# ArduHoop.net
KiCad netlist of a schematic drawn in Altium Designer
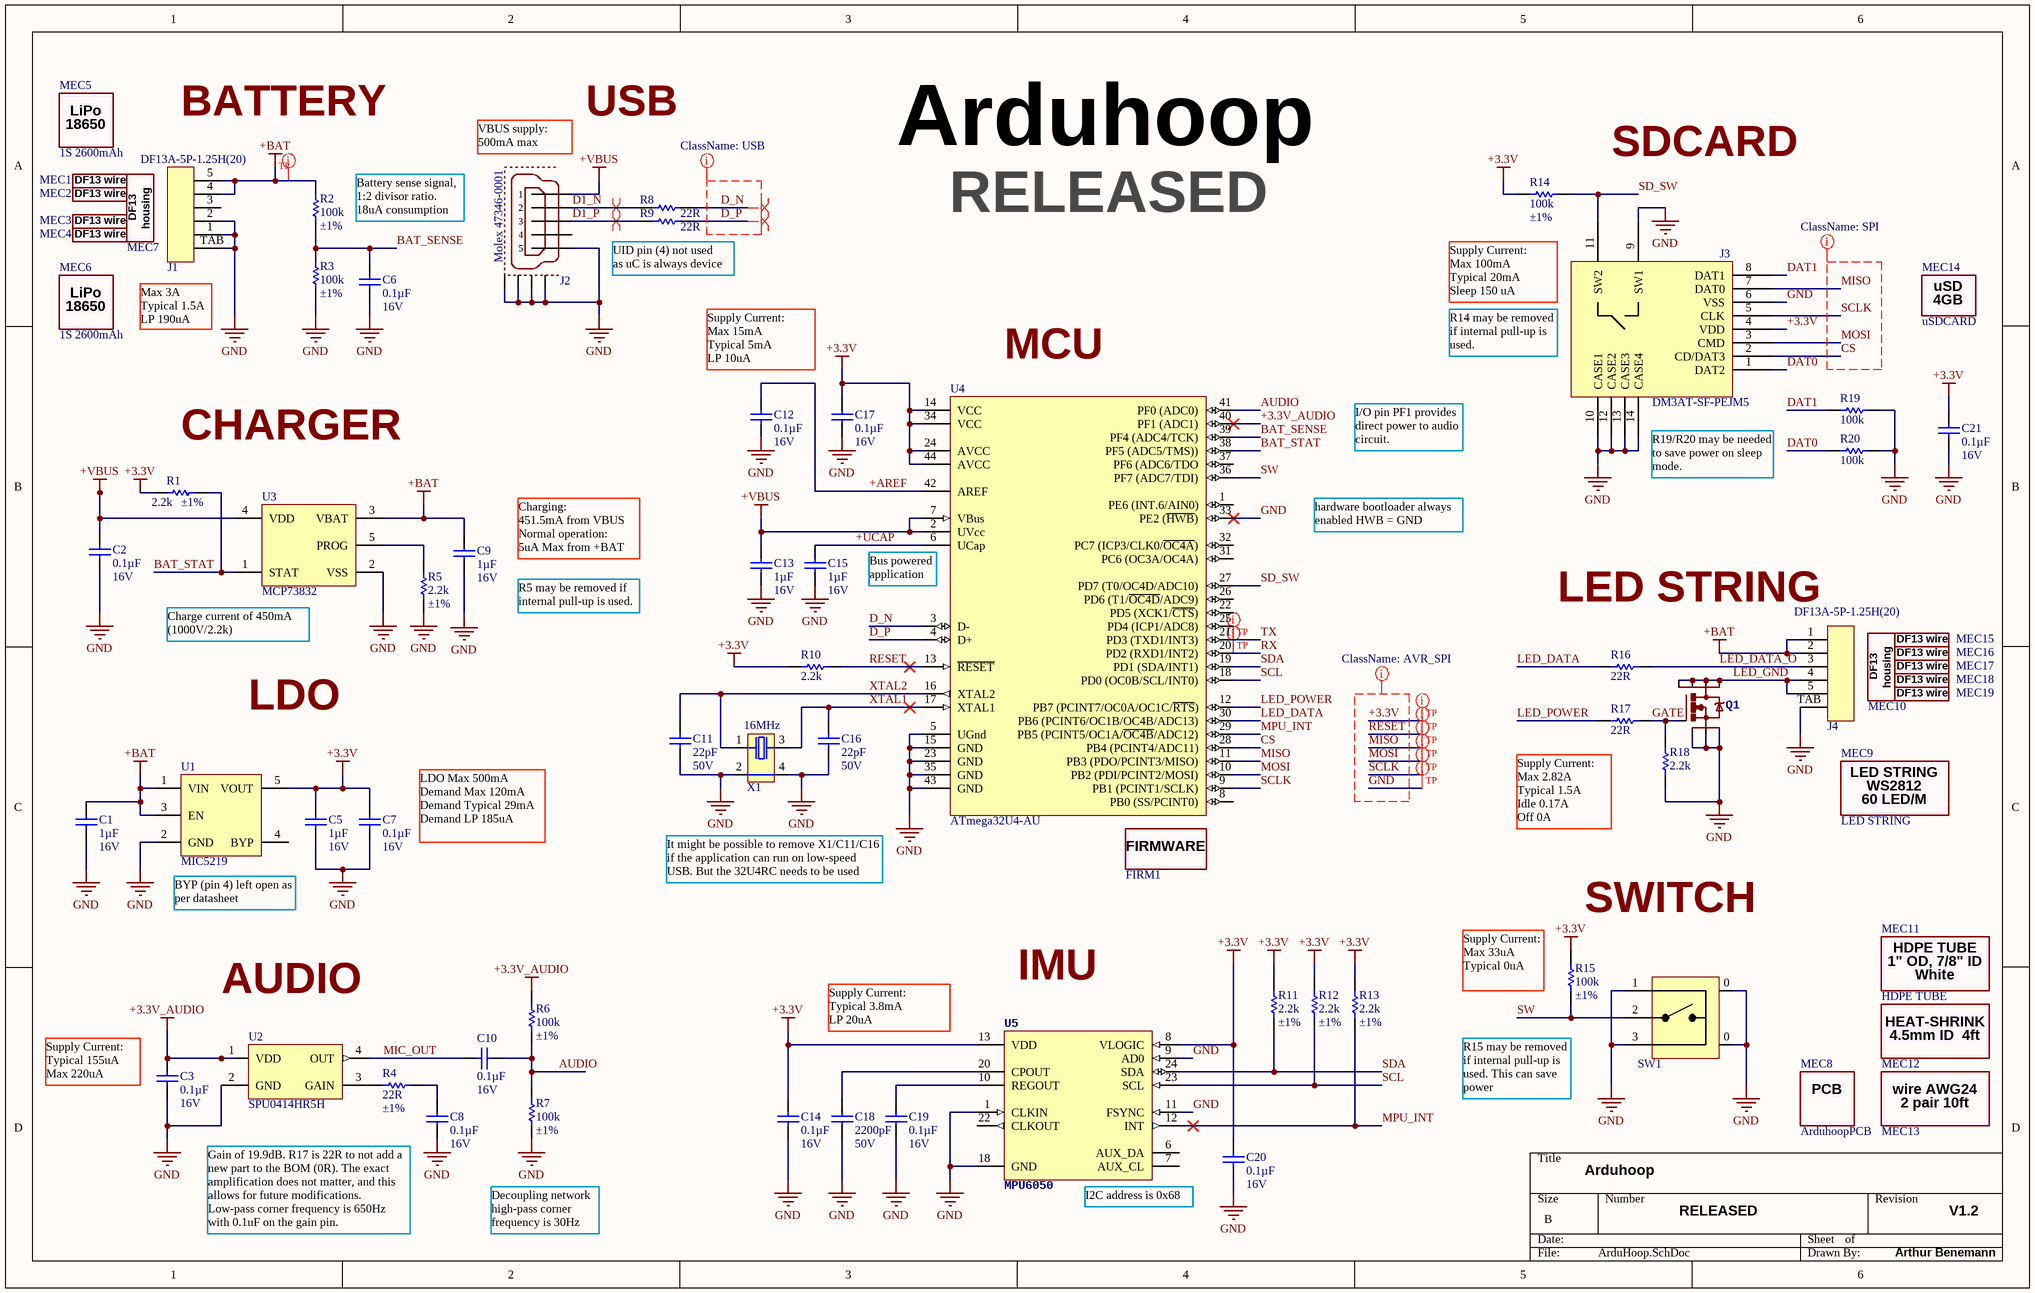
[diagram p0: ArduHoop.SchDoc]

(export (version "E")
  (design (tool "Eeschema 10.0.6"))
  (components
    (comp (ref "C1")
      (value "1µF")
      (footprint "C0603")
      (description "CAP CER 1UF 16V X7R 0603")
      (fields
        (field (name "VOLTAGE") "16V")
        (field (name "PART NUMBER") "C01293")
        (field (name "MANUFACTURER") "Murata Electronics North America")
      )
      (libsource (lib "open-components") (part "CAP"))
    )
    (comp (ref "C2")
      (value "0.1µF")
      (footprint "C0603")
      (description "CAP CER 0.1UF 16V X7R 0603")
      (fields
        (field (name "VOLTAGE") "16V")
        (field (name "PART NUMBER") "C01052")
        (field (name "MANUFACTURER") "Murata Electronics North America")
      )
      (libsource (lib "open-components") (part "CAP"))
    )
    (comp (ref "C3")
      (value "0.1µF")
      (footprint "C0603")
      (description "CAP CER 0.1UF 16V X7R 0603")
      (fields
        (field (name "VOLTAGE") "16V")
        (field (name "PART NUMBER") "C01052")
        (field (name "MANUFACTURER") "Murata Electronics North America")
      )
      (libsource (lib "open-components") (part "CAP"))
    )
    (comp (ref "C5")
      (value "1µF")
      (footprint "C0603")
      (description "CAP CER 1UF 16V X7R 0603")
      (fields
        (field (name "VOLTAGE") "16V")
        (field (name "PART NUMBER") "C01293")
        (field (name "MANUFACTURER") "Murata Electronics North America")
      )
      (libsource (lib "open-components") (part "CAP"))
    )
    (comp (ref "C6")
      (value "0.1µF")
      (footprint "C0603")
      (description "CAP CER 0.1UF 16V X7R 0603")
      (fields
        (field (name "VOLTAGE") "16V")
        (field (name "PART NUMBER") "C01052")
        (field (name "MANUFACTURER") "Murata Electronics North America")
      )
      (libsource (lib "open-components") (part "CAP"))
    )
    (comp (ref "C7")
      (value "0.1µF")
      (footprint "C0603")
      (description "CAP CER 0.1UF 16V X7R 0603")
      (fields
        (field (name "VOLTAGE") "16V")
        (field (name "PART NUMBER") "C01052")
        (field (name "MANUFACTURER") "Murata Electronics North America")
      )
      (libsource (lib "open-components") (part "CAP"))
    )
    (comp (ref "C8")
      (value "0.1µF")
      (footprint "C0603")
      (description "CAP CER 0.1UF 16V X7R 0603")
      (fields
        (field (name "VOLTAGE") "16V")
        (field (name "PART NUMBER") "C01052")
        (field (name "MANUFACTURER") "Murata Electronics North America")
      )
      (libsource (lib "open-components") (part "CAP"))
    )
    (comp (ref "C9")
      (value "1µF")
      (footprint "C0603")
      (description "CAP CER 1UF 16V X7R 0603")
      (fields
        (field (name "VOLTAGE") "16V")
        (field (name "PART NUMBER") "C01293")
        (field (name "MANUFACTURER") "Murata Electronics North America")
      )
      (libsource (lib "open-components") (part "CAP"))
    )
    (comp (ref "C10")
      (value "0.1µF")
      (footprint "C0603")
      (description "CAP CER 0.1UF 16V X7R 0603")
      (fields
        (field (name "VOLTAGE") "16V")
        (field (name "PART NUMBER") "C01052")
        (field (name "MANUFACTURER") "Murata Electronics North America")
      )
      (libsource (lib "open-components") (part "CAP"))
    )
    (comp (ref "C11")
      (value "22pF")
      (footprint "C0603")
      (description "CAP CER 22PF 50V NP0 0603")
      (fields
        (field (name "VOLTAGE") "50V")
        (field (name "PART NUMBER") "C00144")
        (field (name "MANUFACTURER") "Murata Electronics North America")
      )
      (libsource (lib "open-components") (part "CAP"))
    )
    (comp (ref "C12")
      (value "0.1µF")
      (footprint "C0603")
      (description "CAP CER 0.1UF 16V X7R 0603")
      (fields
        (field (name "VOLTAGE") "16V")
        (field (name "PART NUMBER") "C01052")
        (field (name "MANUFACTURER") "Murata Electronics North America")
      )
      (libsource (lib "open-components") (part "CAP"))
    )
    (comp (ref "C13")
      (value "1µF")
      (footprint "C0603")
      (description "CAP CER 1UF 16V X7R 0603")
      (fields
        (field (name "VOLTAGE") "16V")
        (field (name "PART NUMBER") "C01293")
        (field (name "MANUFACTURER") "Murata Electronics North America")
      )
      (libsource (lib "open-components") (part "CAP"))
    )
    (comp (ref "C14")
      (value "0.1µF")
      (footprint "C0603")
      (description "CAP CER 0.1UF 16V X7R 0603")
      (fields
        (field (name "VOLTAGE") "16V")
        (field (name "PART NUMBER") "C01052")
        (field (name "MANUFACTURER") "Murata Electronics North America")
      )
      (libsource (lib "open-components") (part "CAP"))
    )
    (comp (ref "C15")
      (value "1µF")
      (footprint "C0603")
      (description "CAP CER 1UF 16V X7R 0603")
      (fields
        (field (name "VOLTAGE") "16V")
        (field (name "PART NUMBER") "C01293")
        (field (name "MANUFACTURER") "Murata Electronics North America")
      )
      (libsource (lib "open-components") (part "CAP"))
    )
    (comp (ref "C16")
      (value "22pF")
      (footprint "C0603")
      (description "CAP CER 22PF 50V NP0 0603")
      (fields
        (field (name "VOLTAGE") "50V")
        (field (name "PART NUMBER") "C00144")
        (field (name "MANUFACTURER") "Murata Electronics North America")
      )
      (libsource (lib "open-components") (part "CAP"))
    )
    (comp (ref "C17")
      (value "0.1µF")
      (footprint "C0603")
      (description "CAP CER 0.1UF 16V X7R 0603")
      (fields
        (field (name "VOLTAGE") "16V")
        (field (name "PART NUMBER") "C01052")
        (field (name "MANUFACTURER") "Murata Electronics North America")
      )
      (libsource (lib "open-components") (part "CAP"))
    )
    (comp (ref "C18")
      (value "2200pF")
      (footprint "C0603")
      (description "CAP CER 2200PF 50V X7R 0603")
      (fields
        (field (name "VOLTAGE") "50V")
        (field (name "PART NUMBER") "C00648")
        (field (name "MANUFACTURER") "Murata Electronics North America")
      )
      (libsource (lib "open-components") (part "CAP"))
    )
    (comp (ref "C19")
      (value "0.1µF")
      (footprint "C0603")
      (description "CAP CER 0.1UF 16V X7R 0603")
      (fields
        (field (name "VOLTAGE") "16V")
        (field (name "PART NUMBER") "C01052")
        (field (name "MANUFACTURER") "Murata Electronics North America")
      )
      (libsource (lib "open-components") (part "CAP"))
    )
    (comp (ref "C20")
      (value "0.1µF")
      (footprint "C0603")
      (description "CAP CER 0.1UF 16V X7R 0603")
      (fields
        (field (name "VOLTAGE") "16V")
        (field (name "PART NUMBER") "C01052")
        (field (name "MANUFACTURER") "Murata Electronics North America")
      )
      (libsource (lib "open-components") (part "CAP"))
    )
    (comp (ref "C21")
      (value "0.1µF")
      (footprint "C0603")
      (description "CAP CER 0.1UF 16V X7R 0603")
      (fields
        (field (name "VOLTAGE") "16V")
        (field (name "PART NUMBER") "C01052")
        (field (name "MANUFACTURER") "Murata Electronics North America")
      )
      (libsource (lib "open-components") (part "CAP"))
    )
    (comp (ref "FIRM1") (value "FIRMWARE") (libsource (lib "extraComponents") (part "FIRMWARE")))
    (comp (ref "J1")
      (value "HDR_TAB_1x5")
      (footprint "DF13A-5P-1.25H")
      (description "CONN HEADER 5POS 1.25MM R/A TIN")
      (fields
        (field (name "PART NUMBER") "J00022")
        (field (name "MANUFACTURER") "Hirose Electric Co Ltd")
        (field (name "MANUFACTURER PART NUMBER") "DF13A-5P-1.25H(20)")
      )
      (libsource (lib "") (part "HDR_TAB_1x5_1"))
    )
    (comp (ref "J2") (value "~") (footprint "Molex 47346-0001") (libsource (lib "3DR") (part "USB")))
    (comp (ref "J3")
      (value "DM3AT-SF-PEJM5")
      (footprint "USD_DM3AT")
      (description "CONN MICRO SD CARD PUSH-PUSH R/A")
      (fields (field (name "PART NUMBER") "J00167") (field (name "MANUFACTURER") "Hirose Electric Co Ltd"))
      (libsource (lib "open-components") (part "uSD_DM3AT-SF-PEJM5"))
    )
    (comp (ref "J4")
      (value "HDR_TAB_1x5")
      (footprint "DF13A-5P-1.25H")
      (description "CONN HEADER 5POS 1.25MM R/A TIN")
      (fields
        (field (name "PART NUMBER") "J00022")
        (field (name "MANUFACTURER") "Hirose Electric Co Ltd")
        (field (name "MANUFACTURER PART NUMBER") "DF13A-5P-1.25H(20)")
      )
      (libsource (lib "open-components") (part "HDR_TAB_1x5"))
    )
    (comp (ref "MEC1")
      (value "wire5inch-df13")
      (description "DF13 pre-crimped 5\" wire")
      (fields
        (field (name "MANUFACTURER") "Hirose Electric Co Ltd")
        (field (name "MANUFACTURER PART NUMBER") "H4BXG-10105-W6")
      )
      (libsource (lib "extraComponents") (part "wire5inch-df13"))
    )
    (comp (ref "MEC2")
      (value "wire5inch-df13")
      (description "DF13 pre-crimped 5\" wire")
      (fields
        (field (name "MANUFACTURER") "Hirose Electric Co Ltd")
        (field (name "MANUFACTURER PART NUMBER") "H4BXG-10105-W6")
      )
      (libsource (lib "extraComponents") (part "wire5inch-df13"))
    )
    (comp (ref "MEC3")
      (value "wire5inch-df13")
      (description "DF13 pre-crimped 5\" wire")
      (fields
        (field (name "MANUFACTURER") "Hirose Electric Co Ltd")
        (field (name "MANUFACTURER PART NUMBER") "H4BXG-10105-W6")
      )
      (libsource (lib "extraComponents") (part "wire5inch-df13"))
    )
    (comp (ref "MEC4")
      (value "wire5inch-df13")
      (description "DF13 pre-crimped 5\" wire")
      (fields
        (field (name "MANUFACTURER") "Hirose Electric Co Ltd")
        (field (name "MANUFACTURER PART NUMBER") "H4BXG-10105-W6")
      )
      (libsource (lib "extraComponents") (part "wire5inch-df13"))
    )
    (comp (ref "MEC5")
      (value "1S 2600mAh")
      (description "Tenergy Li-Ion 18650 3.7V 2600mAh")
      (fields (field (name "MANUFACTURER PART NUMBER") "30011") (field (name "MANUFACTURER") "Tenergy"))
      (libsource (lib "extraComponents") (part "LiPo_18650_2600mAh"))
    )
    (comp (ref "MEC6")
      (value "1S 2600mAh")
      (description "Tenergy Li-Ion 18650 3.7V 2600mAh")
      (fields (field (name "MANUFACTURER PART NUMBER") "30011") (field (name "MANUFACTURER") "Tenergy"))
      (libsource (lib "extraComponents") (part "LiPo_18650_2600mAh"))
    )
    (comp (ref "MEC7")
      (value "df13housing")
      (description "DF13 housing 5pos")
      (fields
        (field (name "MANUFACTURER") "Hirose Electric Co Ltd")
        (field (name "MANUFACTURER PART NUMBER") "H4BXG-10105-W6")
      )
      (libsource (lib "extraComponents") (part "df13housing"))
    )
    (comp (ref "MEC8")
      (value "ArduhoopPCB")
      (description "PCB")
      (libsource (lib "extraComponents") (part "PCB"))
    )
    (comp (ref "MEC9")
      (value "LED STRING")
      (description "LED Strip WS2812B 60 LEDs/meter")
      (libsource (lib "") (part "LED_STRING1_1"))
    )
    (comp (ref "MEC10")
      (value "df13housing")
      (description "DF13 housing 5pos")
      (fields
        (field (name "MANUFACTURER") "Hirose Electric Co Ltd")
        (field (name "MANUFACTURER PART NUMBER") "H4BXG-10105-W6")
      )
      (libsource (lib "extraComponents") (part "df13housing"))
    )
    (comp (ref "MEC11")
      (value "HDPE TUBE")
      (description "HDPE TUBE 1\" OD, 7/8\" ID White 10 ft")
      (libsource (lib "extraComponents") (part "TUBE_HDPE"))
    )
    (comp (ref "MEC12")
      (value "heatshrink")
      (description "HEAT-SHRINK 3/16\" ID Before, 3/32\" ID After, 4' Length")
      (libsource (lib "extraComponents") (part "heatshrink"))
    )
    (comp (ref "MEC13")
      (value "WIRE AWG24")
      (description "WIRE AWG24 2 conductors")
      (libsource (lib "extraComponents") (part "WIRE_AWG24"))
    )
    (comp (ref "MEC14")
      (value "uSDCARD")
      (description "Sandisk 4GB microSDHC Card Class 2")
      (libsource (lib "extraComponents") (part "LED_STRING1"))
    )
    (comp (ref "MEC15")
      (value "wire5inch-df13")
      (description "DF13 pre-crimped 5\" wire")
      (fields
        (field (name "MANUFACTURER") "Hirose Electric Co Ltd")
        (field (name "MANUFACTURER PART NUMBER") "H4BXG-10105-W6")
      )
      (libsource (lib "extraComponents") (part "wire5inch-df13"))
    )
    (comp (ref "MEC16")
      (value "wire5inch-df13")
      (description "DF13 pre-crimped 5\" wire")
      (fields
        (field (name "MANUFACTURER") "Hirose Electric Co Ltd")
        (field (name "MANUFACTURER PART NUMBER") "H4BXG-10105-W6")
      )
      (libsource (lib "extraComponents") (part "wire5inch-df13"))
    )
    (comp (ref "MEC17")
      (value "wire5inch-df13")
      (description "DF13 pre-crimped 5\" wire")
      (fields
        (field (name "MANUFACTURER") "Hirose Electric Co Ltd")
        (field (name "MANUFACTURER PART NUMBER") "H4BXG-10105-W6")
      )
      (libsource (lib "extraComponents") (part "wire5inch-df13"))
    )
    (comp (ref "MEC18")
      (value "wire5inch-df13")
      (description "DF13 pre-crimped 5\" wire")
      (fields
        (field (name "MANUFACTURER") "Hirose Electric Co Ltd")
        (field (name "MANUFACTURER PART NUMBER") "H4BXG-10105-W6")
      )
      (libsource (lib "extraComponents") (part "wire5inch-df13"))
    )
    (comp (ref "MEC19")
      (value "wire5inch-df13")
      (description "DF13 pre-crimped 5\" wire")
      (fields
        (field (name "MANUFACTURER") "Hirose Electric Co Ltd")
        (field (name "MANUFACTURER PART NUMBER") "H4BXG-10105-W6")
      )
      (libsource (lib "extraComponents") (part "wire5inch-df13"))
    )
    (comp (ref "Q1")
      (value "MOSFET_N")
      (footprint "SO-8")
      (description "MOSFET P-CH 30V 5.8A 8-SOIC")
      (fields (field (name "PART NUMBER") "Q000008") (field (name "MANUFACTURER PART NUMBER") "IRF7406TRPBF"))
      (libsource (lib "open-components") (part "MOSFET_N"))
    )
    (comp (ref "R1")
      (value "2.2k")
      (footprint "R0603")
      (description "RES SMD 2.2K OHM 1% 1/10W 0603")
      (fields
        (field (name "TOLERANCE") "±1%")
        (field (name "PART NUMBER") "R00109")
        (field (name "MANUFACTURER") "Yageo")
      )
      (libsource (lib "open-components") (part "RES"))
    )
    (comp (ref "R2")
      (value "100k")
      (footprint "R0603")
      (description "RES SMD 100K OHM 1% 1/10W 0603")
      (fields
        (field (name "TOLERANCE") "±1%")
        (field (name "PART NUMBER") "R00189")
        (field (name "MANUFACTURER") "Yageo")
      )
      (libsource (lib "open-components") (part "RES"))
    )
    (comp (ref "R3")
      (value "100k")
      (footprint "R0603")
      (description "RES SMD 100K OHM 1% 1/10W 0603")
      (fields
        (field (name "TOLERANCE") "±1%")
        (field (name "PART NUMBER") "R00189")
        (field (name "MANUFACTURER") "Yageo")
      )
      (libsource (lib "open-components") (part "RES"))
    )
    (comp (ref "R4")
      (value "22R")
      (footprint "R0603")
      (description "RES SMD 22 OHM 1% 1/10W 0603")
      (fields
        (field (name "TOLERANCE") "±1%")
        (field (name "PART NUMBER") "R00015")
        (field (name "MANUFACTURER") "Yageo")
      )
      (libsource (lib "open-components") (part "RES"))
    )
    (comp (ref "R5")
      (value "2.2k")
      (footprint "R0603")
      (description "RES SMD 2.2K OHM 1% 1/10W 0603")
      (fields
        (field (name "TOLERANCE") "±1%")
        (field (name "PART NUMBER") "R00109")
        (field (name "MANUFACTURER") "Yageo")
      )
      (libsource (lib "open-components") (part "RES"))
    )
    (comp (ref "R6")
      (value "100k")
      (footprint "R0603")
      (description "RES SMD 100K OHM 1% 1/10W 0603")
      (fields
        (field (name "TOLERANCE") "±1%")
        (field (name "PART NUMBER") "R00189")
        (field (name "MANUFACTURER") "Yageo")
      )
      (libsource (lib "open-components") (part "RES"))
    )
    (comp (ref "R7")
      (value "100k")
      (footprint "R0603")
      (description "RES SMD 100K OHM 1% 1/10W 0603")
      (fields
        (field (name "TOLERANCE") "±1%")
        (field (name "PART NUMBER") "R00189")
        (field (name "MANUFACTURER") "Yageo")
      )
      (libsource (lib "open-components") (part "RES"))
    )
    (comp (ref "R8")
      (value "22R")
      (footprint "R0603")
      (description "RES SMD 22 OHM 1% 1/10W 0603")
      (fields (field (name "TOLERANCE") "±1%") (field (name "PART NUMBER") "R00015"))
      (libsource (lib "open-components") (part "RES"))
    )
    (comp (ref "R9")
      (value "22R")
      (footprint "R0603")
      (description "RES SMD 22 OHM 1% 1/10W 0603")
      (fields (field (name "TOLERANCE") "±1%") (field (name "PART NUMBER") "R00015"))
      (libsource (lib "open-components") (part "RES"))
    )
    (comp (ref "R10")
      (value "2.2k")
      (footprint "R0603")
      (description "RES SMD 2.2K OHM 1% 1/10W 0603")
      (fields (field (name "PART NUMBER") "R00109") (field (name "MANUFACTURER") "Yageo"))
      (libsource (lib "open-components") (part "RES"))
    )
    (comp (ref "R11")
      (value "2.2k")
      (footprint "R0603")
      (description "RES SMD 2.2K OHM 1% 1/10W 0603")
      (fields
        (field (name "TOLERANCE") "±1%")
        (field (name "PART NUMBER") "R00109")
        (field (name "MANUFACTURER") "Yageo")
      )
      (libsource (lib "open-components") (part "RES"))
    )
    (comp (ref "R12")
      (value "2.2k")
      (footprint "R0603")
      (description "RES SMD 2.2K OHM 1% 1/10W 0603")
      (fields
        (field (name "TOLERANCE") "±1%")
        (field (name "PART NUMBER") "R00109")
        (field (name "MANUFACTURER") "Yageo")
      )
      (libsource (lib "open-components") (part "RES"))
    )
    (comp (ref "R13")
      (value "2.2k")
      (footprint "R0603")
      (description "RES SMD 2.2K OHM 1% 1/10W 0603")
      (fields
        (field (name "TOLERANCE") "±1%")
        (field (name "PART NUMBER") "R00109")
        (field (name "MANUFACTURER") "Yageo")
      )
      (libsource (lib "open-components") (part "RES"))
    )
    (comp (ref "R14")
      (value "100k")
      (footprint "R0603")
      (description "RES SMD 100K OHM 1% 1/10W 0603")
      (fields
        (field (name "TOLERANCE") "±1%")
        (field (name "PART NUMBER") "R00189")
        (field (name "MANUFACTURER") "Yageo")
      )
      (libsource (lib "open-components") (part "RES"))
    )
    (comp (ref "R15")
      (value "100k")
      (footprint "R0603")
      (description "RES SMD 100K OHM 1% 1/10W 0603")
      (fields
        (field (name "TOLERANCE") "±1%")
        (field (name "PART NUMBER") "R00189")
        (field (name "MANUFACTURER") "Yageo")
      )
      (libsource (lib "open-components") (part "RES"))
    )
    (comp (ref "R16")
      (value "22R")
      (footprint "R0603")
      (description "RES SMD 22 OHM 1% 1/10W 0603")
      (fields (field (name "PART NUMBER") "R00015") (field (name "MANUFACTURER") "Yageo"))
      (libsource (lib "open-components") (part "RES"))
    )
    (comp (ref "R17")
      (value "22R")
      (footprint "R0603")
      (description "RES SMD 22 OHM 1% 1/10W 0603")
      (fields (field (name "PART NUMBER") "R00015") (field (name "MANUFACTURER") "Yageo"))
      (libsource (lib "open-components") (part "RES"))
    )
    (comp (ref "R18")
      (value "2.2k")
      (footprint "R0603")
      (description "RES SMD 2.2K OHM 1% 1/10W 0603")
      (fields (field (name "PART NUMBER") "R00109") (field (name "MANUFACTURER") "Yageo"))
      (libsource (lib "open-components") (part "RES"))
    )
    (comp (ref "R19")
      (value "100k")
      (footprint "R0603")
      (description "RES SMD 100K OHM 1% 1/10W 0603")
      (fields (field (name "PART NUMBER") "R00189") (field (name "MANUFACTURER") "Yageo"))
      (libsource (lib "open-components") (part "RES"))
    )
    (comp (ref "R20")
      (value "100k")
      (footprint "R0603")
      (description "RES SMD 100K OHM 1% 1/10W 0603")
      (fields (field (name "PART NUMBER") "R00189") (field (name "MANUFACTURER") "Yageo"))
      (libsource (lib "open-components") (part "RES"))
    )
    (comp (ref "SW1")
      (value "EVPAE")
      (footprint "EVPAEJB2A")
      (description "SWITCH TACTILE SPST-NO 0.02A 15V")
      (fields
        (field (name "PART NUMBER") "SW000001")
        (field (name "MANUFACTURER") "Panasonic Electronic Components")
      )
      (libsource (lib "open-components") (part "EVPAE"))
    )
    (comp (ref "U1")
      (value "MIC5219")
      (footprint "SOT-23-5")
      (description "IC REG LDO 3.3V 0.5A SOT23-5")
      (fields
        (field (name "PART NUMBER") "PMIC000001")
        (field (name "MANUFACTURER PART NUMBER") "MIC5219-3.3YM5-TR")
      )
      (libsource (lib "open-components") (part "MIC5219"))
    )
    (comp (ref "U2")
      (value "SPU0414HR5H")
      (footprint "SPU0414HR5H")
      (description "MIC MEMS ANALOG OMNI -22DB")
      (fields
        (field (name "PART NUMBER") "P000005")
        (field (name "MANUFACTURER PART NUMBER") "SPU0414HR5H-SB-7")
      )
      (libsource (lib "open-components") (part "SPU0414HR5H"))
    )
    (comp (ref "U3")
      (value "MCP73832")
      (footprint "SOT-23-5")
      (description "IC LI-ION/LI-POLY CTRLR SOT23-5")
      (fields
        (field (name "PART NUMBER") "P000002")
        (field (name "MANUFACTURER PART NUMBER") "MCP73832T-2ATI/OT")
      )
      (libsource (lib "open-components") (part "MCP7383x"))
    )
    (comp (ref "U4")
      (value "ATmega32U4-AU")
      (footprint "ATMEL-TQFP44_ml")
      (description "IC MCU 8BIT 32KB FLASH 44TQFP")
      (fields
        (field (name "PART NUMBER") "MCU00751")
        (field (name "MANUFACTURER PART NUMBER") "ATMEGA32U4-AUR")
      )
      (libsource (lib "open-components") (part "ATmega32U4-AU"))
    )
    (comp (ref "U5")
      (value "MPU6050")
      (footprint "QFN24_4X4X0.9mm")
      (description "GYRO/ACCELEROMETER 6AXIS 24QFN")
      (fields (field (name "PART NUMBER") "P000004") (field (name "MANUFACTURER PART NUMBER") "MPU-6050"))
      (libsource (lib "open-components") (part "MPU6050"))
    )
    (comp (ref "X1")
      (value "Crystal_4pin")
      (footprint "SMD4_3.2x2.50mm_ABM8")
      (description "CRYSTAL 16.0000MHZ 18PF SMD")
      (fields
        (field (name "PART NUMBER") "Q00342")
        (field (name "MANUFACTURER PART NUMBER") "ABM8-16.000MHZ-B2-T")
        (field (name "FREQUENCY") "16MHz")
      )
      (libsource (lib "open-components") (part "Crystal_4pin"))
    )
  )
  (nets
    (net (code "1") (name "+3.3V") (class "Default")
      (node (ref "C14") (pin "1") (pinfunction "1_1") (pintype "passive"))
      (node (ref "C17") (pin "1") (pinfunction "1_1") (pintype "passive"))
      (node (ref "C20") (pin "1") (pinfunction "1_1") (pintype "passive"))
      (node (ref "C21") (pin "1") (pinfunction "1_1") (pintype "passive"))
      (node (ref "C5") (pin "1") (pinfunction "1_1") (pintype "passive"))
      (node (ref "C7") (pin "1") (pinfunction "1_1") (pintype "passive"))
      (node (ref "J3") (pin "4") (pinfunction "VDD_4") (pintype "passive"))
      (node (ref "R1") (pin "1") (pinfunction "1_1") (pintype "passive"))
      (node (ref "R10") (pin "1") (pinfunction "1_1") (pintype "passive"))
      (node (ref "R11") (pin "1") (pinfunction "1_1") (pintype "passive"))
      (node (ref "R12") (pin "1") (pinfunction "1_1") (pintype "passive"))
      (node (ref "R13") (pin "1") (pinfunction "1_1") (pintype "passive"))
      (node (ref "R14") (pin "2") (pinfunction "2_2") (pintype "passive"))
      (node (ref "R15") (pin "2") (pinfunction "2_2") (pintype "passive"))
      (node (ref "U1") (pin "5") (pinfunction "VOUT_5") (pintype "power_in"))
      (node (ref "U4") (pin "14") (pinfunction "VCC_14") (pintype "power_in"))
      (node (ref "U4") (pin "24") (pinfunction "AVCC_24") (pintype "power_in"))
      (node (ref "U4") (pin "34") (pinfunction "VCC_34") (pintype "power_in"))
      (node (ref "U4") (pin "44") (pinfunction "AVCC_44") (pintype "power_in"))
      (node (ref "U5") (pin "13") (pinfunction "VDD_13") (pintype "power_in"))
      (node (ref "U5") (pin "8") (pinfunction "VLOGIC_8") (pintype "input"))
    )
    (net (code "2") (name "+3.3V_AUDIO") (class "Default")
      (node (ref "C3") (pin "1") (pinfunction "1_1") (pintype "passive"))
      (node (ref "R6") (pin "2") (pinfunction "2_2") (pintype "passive"))
      (node (ref "U2") (pin "1") (pinfunction "VDD_1") (pintype "power_in"))
      (node (ref "U4") (pin "40") (pinfunction "PF1_(ADC1)_40") (pintype "bidirectional"))
    )
    (net (code "3") (name "+BAT") (class "Default")
      (node (ref "C1") (pin "1") (pinfunction "1_1") (pintype "passive"))
      (node (ref "C9") (pin "1") (pinfunction "1_1") (pintype "passive"))
      (node (ref "J1") (pin "4") (pinfunction "4_4") (pintype "passive"))
      (node (ref "J1") (pin "5") (pinfunction "5_5") (pintype "passive"))
      (node (ref "J4") (pin "1") (pinfunction "1_1") (pintype "passive"))
      (node (ref "J4") (pin "2") (pinfunction "2_2") (pintype "passive"))
      (node (ref "R2") (pin "2") (pinfunction "2_2") (pintype "passive"))
      (node (ref "U1") (pin "1") (pinfunction "VIN_1") (pintype "power_in"))
      (node (ref "U1") (pin "3") (pinfunction "EN_3") (pintype "passive"))
      (node (ref "U3") (pin "3") (pinfunction "VBAT_3") (pintype "passive"))
    )
    (net (code "4") (name "+VBUS") (class "Default")
      (node (ref "C13") (pin "1") (pinfunction "1_1") (pintype "passive"))
      (node (ref "C2") (pin "1") (pinfunction "1_1") (pintype "passive"))
      (node (ref "J2") (pin "VBUS") (pinfunction "1_VBUS") (pintype "power_in"))
      (node (ref "U3") (pin "4") (pinfunction "VDD_4") (pintype "power_in"))
      (node (ref "U4") (pin "2") (pinfunction "UVcc_2") (pintype "power_in"))
      (node (ref "U4") (pin "7") (pinfunction "VBus_7") (pintype "input"))
    )
    (net (code "5") (name "/+AREF") (class "Default")
      (node (ref "C12") (pin "1") (pinfunction "1_1") (pintype "passive"))
      (node (ref "U4") (pin "42") (pinfunction "AREF_42") (pintype "passive"))
    )
    (net (code "6") (name "/+UCAP") (class "Default")
      (node (ref "C15") (pin "1") (pinfunction "1_1") (pintype "passive"))
      (node (ref "U4") (pin "6") (pinfunction "UCap_6") (pintype "passive"))
    )
    (net (code "7") (name "/AUDIO") (class "Default")
      (node (ref "C10") (pin "2") (pinfunction "2_2") (pintype "passive"))
      (node (ref "R6") (pin "1") (pinfunction "1_1") (pintype "passive"))
      (node (ref "R7") (pin "2") (pinfunction "2_2") (pintype "passive"))
      (node (ref "U4") (pin "41") (pinfunction "PF0_(ADC0)_41") (pintype "bidirectional"))
    )
    (net (code "8") (name "/BAT_SENSE") (class "Default")
      (node (ref "C6") (pin "1") (pinfunction "1_1") (pintype "passive"))
      (node (ref "R2") (pin "1") (pinfunction "1_1") (pintype "passive"))
      (node (ref "R3") (pin "2") (pinfunction "2_2") (pintype "passive"))
      (node (ref "U4") (pin "39") (pinfunction "PF4_(ADC4/TCK)_39") (pintype "bidirectional"))
    )
    (net (code "9") (name "/BAT_STAT") (class "Default")
      (node (ref "R1") (pin "2") (pinfunction "2_2") (pintype "passive"))
      (node (ref "U3") (pin "1") (pinfunction "STAT_1") (pintype "passive"))
      (node (ref "U4") (pin "38") (pinfunction "PF5_(ADC5/TMS))_38") (pintype "bidirectional"))
    )
    (net (code "10") (name "/CS") (class "Default")
      (node (ref "J3") (pin "2") (pinfunction "CD/DAT3_2") (pintype "passive"))
      (node (ref "U4") (pin "28") (pinfunction "PB4_(PCINT4/ADC11)_28") (pintype "bidirectional"))
    )
    (net (code "11") (name "/D1_N") (class "Default")
      (node (ref "J2") (pin "D-") (pinfunction "2_D-") (pintype "passive"))
      (node (ref "R8") (pin "1") (pinfunction "1_1") (pintype "passive"))
    )
    (net (code "12") (name "/D1_P") (class "Default")
      (node (ref "J2") (pin "D+") (pinfunction "3_D+") (pintype "passive"))
      (node (ref "R9") (pin "1") (pinfunction "1_1") (pintype "passive"))
    )
    (net (code "13") (name "/DAT0") (class "Default")
      (node (ref "J3") (pin "1") (pinfunction "DAT2_1") (pintype "passive"))
      (node (ref "R20") (pin "2") (pinfunction "2_2") (pintype "passive"))
    )
    (net (code "14") (name "/DAT1") (class "Default")
      (node (ref "J3") (pin "8") (pinfunction "DAT1_8") (pintype "passive"))
      (node (ref "R19") (pin "2") (pinfunction "2_2") (pintype "passive"))
    )
    (net (code "15") (name "/D_N") (class "Default")
      (node (ref "R8") (pin "2") (pinfunction "2_2") (pintype "passive"))
      (node (ref "U4") (pin "3") (pinfunction "D-_3") (pintype "bidirectional"))
    )
    (net (code "16") (name "/D_P") (class "Default")
      (node (ref "R9") (pin "2") (pinfunction "2_2") (pintype "passive"))
      (node (ref "U4") (pin "4") (pinfunction "D+_4") (pintype "bidirectional"))
    )
    (net (code "17") (name "/GATE") (class "Default")
      (node (ref "Q1") (pin "4") (pinfunction "G_4") (pintype "passive"))
      (node (ref "R17") (pin "2") (pinfunction "2_2") (pintype "passive"))
      (node (ref "R18") (pin "1") (pinfunction "1_1") (pintype "passive"))
    )
    (net (code "18") (name "/LED_DATA") (class "Default")
      (node (ref "R16") (pin "1") (pinfunction "1_1") (pintype "passive"))
      (node (ref "U4") (pin "30") (pinfunction "PB6_(PCINT6/OC1B/OC4B/ADC13)_30") (pintype "bidirectional"))
    )
    (net (code "19") (name "/LED_DATA_O") (class "Default")
      (node (ref "J4") (pin "3") (pinfunction "3_3") (pintype "passive"))
      (node (ref "R16") (pin "2") (pinfunction "2_2") (pintype "passive"))
    )
    (net (code "20") (name "/LED_GND") (class "Default")
      (node (ref "J4") (pin "4") (pinfunction "4_4") (pintype "passive"))
      (node (ref "J4") (pin "5") (pinfunction "5_5") (pintype "passive"))
      (node (ref "Q1") (pin "5") (pinfunction "D_5") (pintype "passive"))
      (node (ref "Q1") (pin "6") (pinfunction "D_6") (pintype "passive"))
      (node (ref "Q1") (pin "7") (pinfunction "D_7") (pintype "passive"))
      (node (ref "Q1") (pin "8") (pinfunction "D_8") (pintype "passive"))
    )
    (net (code "21") (name "/LED_POWER") (class "Default")
      (node (ref "R17") (pin "1") (pinfunction "1_1") (pintype "passive"))
      (node (ref "U4") (pin "12") (pinfunction "PB7_(PCINT7/OC0A/OC1C/~{RTS})_12") (pintype "bidirectional"))
    )
    (net (code "22") (name "/MIC_OUT") (class "Default")
      (node (ref "C10") (pin "1") (pinfunction "1_1") (pintype "passive"))
      (node (ref "U2") (pin "4") (pinfunction "OUT_4") (pintype "output"))
    )
    (net (code "23") (name "/MISO") (class "Default")
      (node (ref "J3") (pin "7") (pinfunction "DAT0_7") (pintype "passive"))
      (node (ref "U4") (pin "11") (pinfunction "PB3_(PDO/PCINT3/MISO)_11") (pintype "bidirectional"))
    )
    (net (code "24") (name "/MOSI") (class "Default")
      (node (ref "J3") (pin "3") (pinfunction "CMD_3") (pintype "passive"))
      (node (ref "U4") (pin "10") (pinfunction "PB2_(PDI/PCINT2/MOSI)_10") (pintype "bidirectional"))
    )
    (net (code "25") (name "/MPU_INT") (class "Default")
      (node (ref "R13") (pin "2") (pinfunction "2_2") (pintype "passive"))
      (node (ref "U4") (pin "29") (pinfunction "PB5_(PCINT5/OC1A/~{OC4B}/ADC12)_29") (pintype "bidirectional"))
      (node (ref "U5") (pin "12") (pinfunction "INT_12") (pintype "output"))
    )
    (net (code "26") (name "/RESET") (class "Default")
      (node (ref "R10") (pin "2") (pinfunction "2_2") (pintype "passive"))
      (node (ref "U4") (pin "13") (pinfunction "~{RESET}_13") (pintype "input"))
    )
    (net (code "27") (name "/RX") (class "Default")
      (node (ref "U4") (pin "20") (pinfunction "PD2_(RXD1/INT2)_20") (pintype "bidirectional"))
    )
    (net (code "28") (name "/SCL") (class "Default")
      (node (ref "R12") (pin "2") (pinfunction "2_2") (pintype "passive"))
      (node (ref "U4") (pin "18") (pinfunction "PD0_(OC0B/SCL/INT0)_18") (pintype "bidirectional"))
      (node (ref "U5") (pin "23") (pinfunction "SCL_23") (pintype "input"))
    )
    (net (code "29") (name "/SCLK") (class "Default")
      (node (ref "J3") (pin "5") (pinfunction "CLK_5") (pintype "passive"))
      (node (ref "U4") (pin "9") (pinfunction "PB1_(PCINT1/SCLK)_9") (pintype "bidirectional"))
    )
    (net (code "30") (name "/SDA") (class "Default")
      (node (ref "R11") (pin "2") (pinfunction "2_2") (pintype "passive"))
      (node (ref "U4") (pin "19") (pinfunction "PD1_(SDA/INT1)_19") (pintype "bidirectional"))
      (node (ref "U5") (pin "24") (pinfunction "SDA_24") (pintype "bidirectional"))
    )
    (net (code "31") (name "/SD_SW") (class "Default")
      (node (ref "J3") (pin "11") (pinfunction "SW2_11") (pintype "passive"))
      (node (ref "R14") (pin "1") (pinfunction "1_1") (pintype "passive"))
      (node (ref "U4") (pin "27") (pinfunction "PD7_(T0/OC4D/ADC10)_27") (pintype "bidirectional"))
    )
    (net (code "32") (name "/SW") (class "Default")
      (node (ref "R15") (pin "1") (pinfunction "1_1") (pintype "passive"))
      (node (ref "SW1") (pin "2") (pintype "passive"))
      (node (ref "U4") (pin "36") (pinfunction "PF7_(ADC7/TDI)_36") (pintype "bidirectional"))
    )
    (net (code "33") (name "/TX") (class "Default")
      (node (ref "U4") (pin "21") (pinfunction "PD3_(TXD1/INT3)_21") (pintype "bidirectional"))
    )
    (net (code "34") (name "/XTAL1") (class "Default")
      (node (ref "C16") (pin "1") (pinfunction "1_1") (pintype "passive"))
      (node (ref "U4") (pin "17") (pinfunction "XTAL1_17") (pintype "input"))
      (node (ref "X1") (pin "3") (pintype "passive"))
    )
    (net (code "35") (name "/XTAL2") (class "Default")
      (node (ref "C11") (pin "1") (pinfunction "1_1") (pintype "passive"))
      (node (ref "U4") (pin "16") (pinfunction "XTAL2_16") (pintype "output"))
      (node (ref "X1") (pin "1") (pintype "passive"))
    )
    (net (code "36") (name "GND") (class "Default")
      (node (ref "C1") (pin "2") (pinfunction "2_2") (pintype "passive"))
      (node (ref "C11") (pin "2") (pinfunction "2_2") (pintype "passive"))
      (node (ref "C12") (pin "2") (pinfunction "2_2") (pintype "passive"))
      (node (ref "C13") (pin "2") (pinfunction "2_2") (pintype "passive"))
      (node (ref "C14") (pin "2") (pinfunction "2_2") (pintype "passive"))
      (node (ref "C15") (pin "2") (pinfunction "2_2") (pintype "passive"))
      (node (ref "C16") (pin "2") (pinfunction "2_2") (pintype "passive"))
      (node (ref "C17") (pin "2") (pinfunction "2_2") (pintype "passive"))
      (node (ref "C18") (pin "2") (pinfunction "2_2") (pintype "passive"))
      (node (ref "C19") (pin "2") (pinfunction "2_2") (pintype "passive"))
      (node (ref "C2") (pin "2") (pinfunction "2_2") (pintype "passive"))
      (node (ref "C20") (pin "2") (pinfunction "2_2") (pintype "passive"))
      (node (ref "C21") (pin "2") (pinfunction "2_2") (pintype "passive"))
      (node (ref "C3") (pin "2") (pinfunction "2_2") (pintype "passive"))
      (node (ref "C5") (pin "2") (pinfunction "2_2") (pintype "passive"))
      (node (ref "C6") (pin "2") (pinfunction "2_2") (pintype "passive"))
      (node (ref "C7") (pin "2") (pinfunction "2_2") (pintype "passive"))
      (node (ref "C8") (pin "2") (pinfunction "2_2") (pintype "passive"))
      (node (ref "C9") (pin "2") (pinfunction "2_2") (pintype "passive"))
      (node (ref "J1") (pin "1") (pinfunction "1_1") (pintype "passive"))
      (node (ref "J1") (pin "2") (pinfunction "2_2") (pintype "passive"))
      (node (ref "J1") (pin "TAB") (pinfunction "TAB_TAB") (pintype "passive"))
      (node (ref "J2") (pin "GND") (pinfunction "5_GND") (pintype "power_in"))
      (node (ref "J2") (pin "GND1") (pinfunction "GND1_GND1") (pintype "passive"))
      (node (ref "J2") (pin "GND2") (pinfunction "GND2_GND2") (pintype "passive"))
      (node (ref "J2") (pin "GND3") (pinfunction "GND3_GND3") (pintype "passive"))
      (node (ref "J2") (pin "GND4") (pinfunction "GND4_GND4") (pintype "passive"))
      (node (ref "J3") (pin "10") (pinfunction "CASE1_10") (pintype "passive"))
      (node (ref "J3") (pin "12") (pinfunction "CASE2_12") (pintype "passive"))
      (node (ref "J3") (pin "13") (pinfunction "CASE3_13") (pintype "passive"))
      (node (ref "J3") (pin "14") (pinfunction "CASE4_14") (pintype "passive"))
      (node (ref "J3") (pin "6") (pinfunction "VSS_6") (pintype "passive"))
      (node (ref "J3") (pin "9") (pinfunction "SW1_9") (pintype "passive"))
      (node (ref "J4") (pin "TAB") (pinfunction "TAB_TAB") (pintype "passive"))
      (node (ref "Q1") (pin "1") (pinfunction "S_1") (pintype "passive"))
      (node (ref "Q1") (pin "2") (pinfunction "S_2") (pintype "passive"))
      (node (ref "Q1") (pin "3") (pinfunction "S_3") (pintype "passive"))
      (node (ref "R18") (pin "2") (pinfunction "2_2") (pintype "passive"))
      (node (ref "R19") (pin "1") (pinfunction "1_1") (pintype "passive"))
      (node (ref "R20") (pin "1") (pinfunction "1_1") (pintype "passive"))
      (node (ref "R3") (pin "1") (pinfunction "1_1") (pintype "passive"))
      (node (ref "R5") (pin "2") (pinfunction "2_2") (pintype "passive"))
      (node (ref "R7") (pin "1") (pinfunction "1_1") (pintype "passive"))
      (node (ref "SW1") (pin "0") (pintype "passive"))
      (node (ref "SW1") (pin "1") (pintype "passive"))
      (node (ref "SW1") (pin "3") (pintype "passive"))
      (node (ref "U1") (pin "2") (pinfunction "GND_2") (pintype "power_in"))
      (node (ref "U2") (pin "2") (pinfunction "GND_2") (pintype "power_in"))
      (node (ref "U3") (pin "2") (pinfunction "VSS_2") (pintype "power_in"))
      (node (ref "U4") (pin "15") (pinfunction "GND_15") (pintype "power_in"))
      (node (ref "U4") (pin "23") (pinfunction "GND_23") (pintype "power_in"))
      (node (ref "U4") (pin "33") (pinfunction "PE2_(~{HWB})_33") (pintype "bidirectional"))
      (node (ref "U4") (pin "35") (pinfunction "GND_35") (pintype "power_in"))
      (node (ref "U4") (pin "43") (pinfunction "GND_43") (pintype "power_in"))
      (node (ref "U4") (pin "5") (pinfunction "UGnd_5") (pintype "power_in"))
      (node (ref "U5") (pin "1") (pinfunction "CLKIN_1") (pintype "input"))
      (node (ref "U5") (pin "11") (pinfunction "FSYNC_11") (pintype "input"))
      (node (ref "U5") (pin "18") (pinfunction "GND_18") (pintype "power_in"))
      (node (ref "U5") (pin "9") (pinfunction "AD0_9") (pintype "input"))
      (node (ref "X1") (pin "2") (pintype "passive"))
      (node (ref "X1") (pin "4") (pintype "passive"))
    )
    (net (code "37") (name "Net-(C8-Pad1)") (class "Default")
      (node (ref "C8") (pin "1") (pinfunction "1_1") (pintype "passive"))
      (node (ref "R4") (pin "2") (pinfunction "2_2") (pintype "passive"))
    )
    (net (code "38") (name "Net-(U2-GAIN)") (class "Default")
      (node (ref "R4") (pin "1") (pinfunction "1_1") (pintype "passive"))
      (node (ref "U2") (pin "3") (pinfunction "GAIN_3") (pintype "passive"))
    )
    (net (code "39") (name "Net-(U3-PROG)") (class "Default")
      (node (ref "R5") (pin "1") (pinfunction "1_1") (pintype "passive"))
      (node (ref "U3") (pin "5") (pinfunction "PROG_5") (pintype "passive"))
    )
    (net (code "40") (name "Net-(U5-CPOUT)") (class "Default")
      (node (ref "C18") (pin "1") (pinfunction "1_1") (pintype "passive"))
      (node (ref "U5") (pin "20") (pinfunction "CPOUT_20") (pintype "passive"))
    )
    (net (code "41") (name "Net-(U5-REGOUT)") (class "Default")
      (node (ref "C19") (pin "1") (pinfunction "1_1") (pintype "passive"))
      (node (ref "U5") (pin "10") (pinfunction "REGOUT_10") (pintype "passive"))
    )
    (net (code "42") (name "unconnected-(J1-Pad3)") (class "Default")
      (node (ref "J1") (pin "3") (pinfunction "3_3") (pintype "passive"))
    )
    (net (code "43") (name "unconnected-(J2-4-PadID)") (class "Default")
      (node (ref "J2") (pin "ID") (pinfunction "4_ID") (pintype "passive"))
    )
    (net (code "44") (name "unconnected-(U1-BYP-Pad4)") (class "Default")
      (node (ref "U1") (pin "4") (pinfunction "BYP_4") (pintype "passive"))
    )
    (net (code "45") (name "unconnected-(U4-PB0_(SS{slash}PCINT0)-Pad8)") (class "Default")
      (node (ref "U4") (pin "8") (pinfunction "PB0_(SS/PCINT0)_8") (pintype "bidirectional"))
    )
    (net (code "46") (name "unconnected-(U4-PC6_(OC3A{slash}OC4A)-Pad31)") (class "Default")
      (node (ref "U4") (pin "31") (pinfunction "PC6_(OC3A/OC4A)_31") (pintype "bidirectional"))
    )
    (net (code "47") (name "unconnected-(U4-PC7_(ICP3{slash}CLK0{slash}~{OC4A})-Pad32)") (class "Default")
      (node (ref "U4") (pin "32") (pinfunction "PC7_(ICP3/CLK0/~{OC4A})_32") (pintype "bidirectional"))
    )
    (net (code "48") (name "unconnected-(U4-PD4_(ICP1{slash}ADC8)-Pad25)") (class "Default")
      (node (ref "U4") (pin "25") (pinfunction "PD4_(ICP1/ADC8)_25") (pintype "bidirectional"))
    )
    (net (code "49") (name "unconnected-(U4-PD5_(XCK1{slash}~{CTS})-Pad22)") (class "Default")
      (node (ref "U4") (pin "22") (pinfunction "PD5_(XCK1/~{CTS})_22") (pintype "bidirectional"))
    )
    (net (code "50") (name "unconnected-(U4-PD6_(T1{slash}~{OC4D}{slash}ADC9)-Pad26)") (class "Default")
      (node (ref "U4") (pin "26") (pinfunction "PD6_(T1/~{OC4D}/ADC9)_26") (pintype "bidirectional"))
    )
    (net (code "51") (name "unconnected-(U4-PE6_(INT.6{slash}AIN0)-Pad1)") (class "Default")
      (node (ref "U4") (pin "1") (pinfunction "PE6_(INT.6/AIN0)_1") (pintype "bidirectional"))
    )
    (net (code "52") (name "unconnected-(U4-PF6_(ADC6{slash}TDO-Pad37)") (class "Default")
      (node (ref "U4") (pin "37") (pinfunction "PF6_(ADC6/TDO_37") (pintype "bidirectional"))
    )
    (net (code "53") (name "unconnected-(U5-AUX_CL-Pad7)") (class "Default")
      (node (ref "U5") (pin "7") (pinfunction "AUX_CL_7") (pintype "passive"))
    )
    (net (code "54") (name "unconnected-(U5-AUX_DA-Pad6)") (class "Default")
      (node (ref "U5") (pin "6") (pinfunction "AUX_DA_6") (pintype "passive"))
    )
    (net (code "55") (name "unconnected-(U5-CLKOUT-Pad22)") (class "Default")
      (node (ref "U5") (pin "22") (pinfunction "CLKOUT_22") (pintype "output"))
    )
  )
)
